# BrickPi_1_7_3.net
KiCad netlist of a schematic drawn in EAGLE
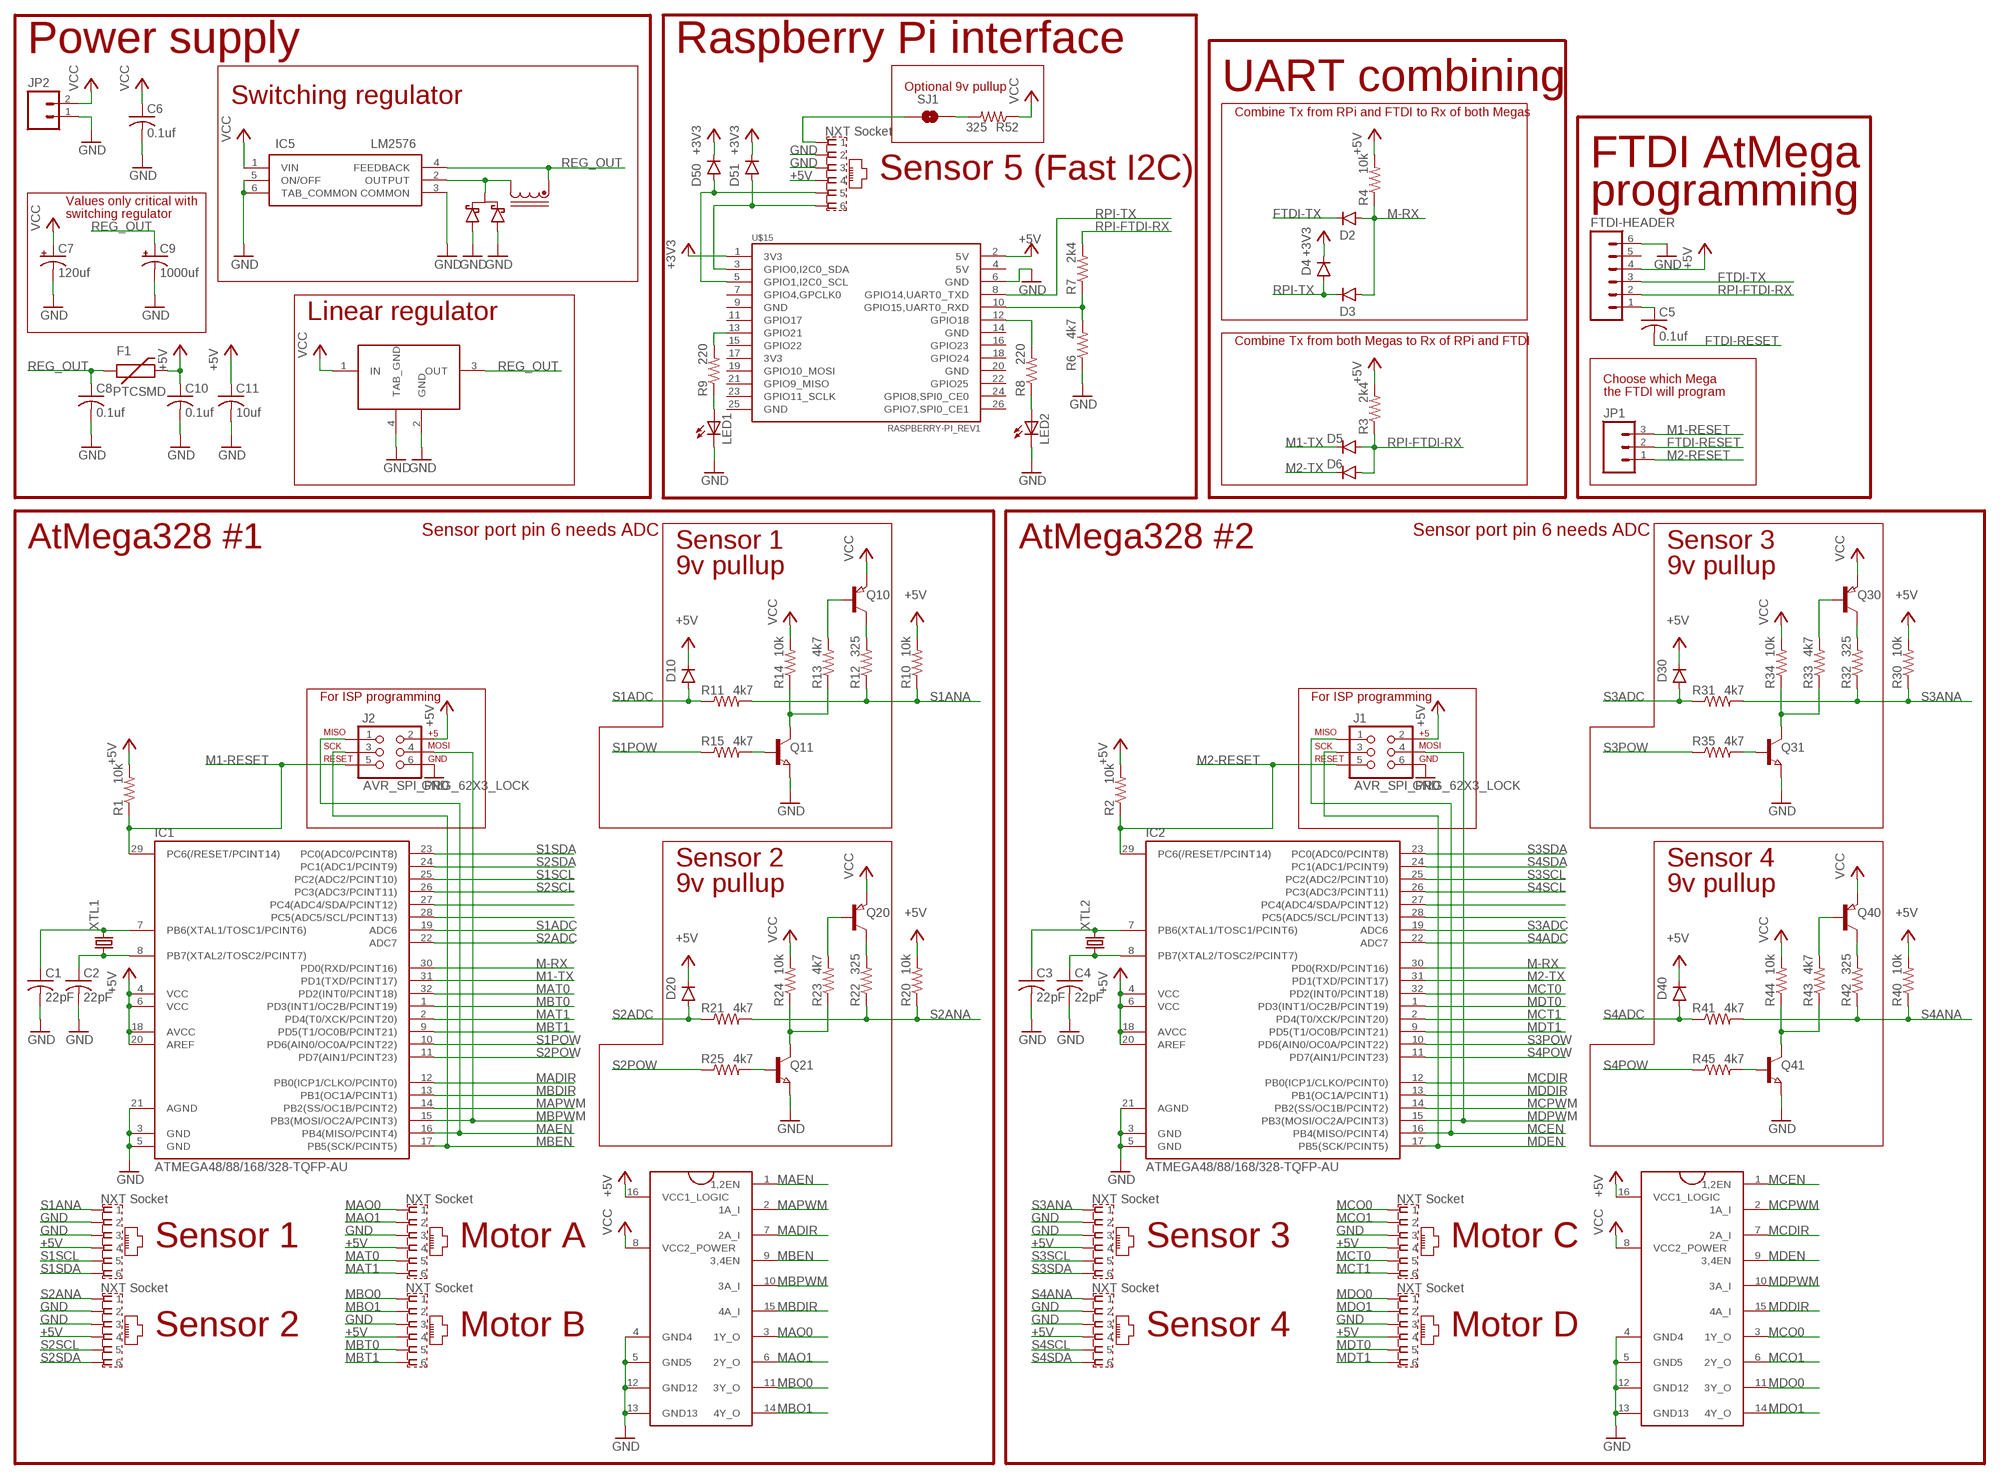
[diagram p0: schematic, sheet 1]

(export (version "E")
  (design (tool "Eeschema 10.0.6"))
  (components
    (comp (ref "C1")
      (value "22pF")
      (footprint "eagle-import:C0805")
      (libsource (lib "eagle-import") (part "C-USC0805"))
    )
    (comp (ref "C2")
      (value "22pF")
      (footprint "eagle-import:C0805")
      (libsource (lib "eagle-import") (part "C-USC0805"))
    )
    (comp (ref "C3")
      (value "22pF")
      (footprint "eagle-import:C0805")
      (libsource (lib "eagle-import") (part "C-USC0805"))
    )
    (comp (ref "C4")
      (value "22pF")
      (footprint "eagle-import:C0805")
      (libsource (lib "eagle-import") (part "C-USC0805"))
    )
    (comp (ref "C5")
      (value "0.1uf")
      (footprint "eagle-import:C0805")
      (libsource (lib "eagle-import") (part "C-USC0805"))
    )
    (comp (ref "C6")
      (value "0.1uf")
      (footprint "eagle-import:C0805")
      (libsource (lib "eagle-import") (part "C-USC0805"))
    )
    (comp (ref "C7")
      (value "120uf")
      (footprint "eagle-import:E2,5-6")
      (libsource (lib "eagle-import") (part "CPOL-USE2.5-6"))
    )
    (comp (ref "C8")
      (value "0.1uf")
      (footprint "eagle-import:C0805")
      (libsource (lib "eagle-import") (part "C-USC0805"))
    )
    (comp (ref "C9")
      (value "1000uf")
      (footprint "eagle-import:E3,5-10")
      (libsource (lib "eagle-import") (part "CPOL-USE3.5-10"))
    )
    (comp (ref "C10")
      (value "0.1uf")
      (footprint "eagle-import:C0805")
      (libsource (lib "eagle-import") (part "C-USC0805"))
    )
    (comp (ref "C11")
      (value "10uf")
      (footprint "eagle-import:C0805")
      (libsource (lib "eagle-import") (part "C-USC0805"))
    )
    (comp (ref "D1")
      (value "DIODE_SCHOTTKY_VS-6CWQ04FNTRPBF")
      (footprint "eagle-import:DPAK")
      (libsource (lib "eagle-import") (part "DIODE_SCHOTTKY_VS-6CWQ04FNTRPBF"))
    )
    (comp (ref "D2")
      (value "DIODESOD80")
      (footprint "eagle-import:SOD80")
      (libsource (lib "eagle-import") (part "DIODESOD80"))
    )
    (comp (ref "D3")
      (value "DIODESOD80")
      (footprint "eagle-import:SOD80")
      (libsource (lib "eagle-import") (part "DIODESOD80"))
    )
    (comp (ref "D4")
      (value "DIODESOD80")
      (footprint "eagle-import:SOD80")
      (libsource (lib "eagle-import") (part "DIODESOD80"))
    )
    (comp (ref "D5")
      (value "DIODESOD80")
      (footprint "eagle-import:SOD80")
      (libsource (lib "eagle-import") (part "DIODESOD80"))
    )
    (comp (ref "D6")
      (value "DIODESOD80")
      (footprint "eagle-import:SOD80")
      (libsource (lib "eagle-import") (part "DIODESOD80"))
    )
    (comp (ref "D10")
      (value "DIODESOD80")
      (footprint "eagle-import:SOD80")
      (libsource (lib "eagle-import") (part "DIODESOD80"))
    )
    (comp (ref "D20")
      (value "DIODESOD80")
      (footprint "eagle-import:SOD80")
      (libsource (lib "eagle-import") (part "DIODESOD80"))
    )
    (comp (ref "D30")
      (value "DIODESOD80")
      (footprint "eagle-import:SOD80")
      (libsource (lib "eagle-import") (part "DIODESOD80"))
    )
    (comp (ref "D40")
      (value "DIODESOD80")
      (footprint "eagle-import:SOD80")
      (libsource (lib "eagle-import") (part "DIODESOD80"))
    )
    (comp (ref "D50")
      (value "DIODESOD80")
      (footprint "eagle-import:SOD80")
      (libsource (lib "eagle-import") (part "DIODESOD80"))
    )
    (comp (ref "D51")
      (value "DIODESOD80")
      (footprint "eagle-import:SOD80")
      (libsource (lib "eagle-import") (part "DIODESOD80"))
    )
    (comp (ref "F1")
      (value "PTCSMD")
      (footprint "eagle-import:PTC-1206")
      (libsource (lib "eagle-import") (part "PTCSMD"))
    )
    (comp (ref "FTDI-HEADER")
      (value "M06LOCK")
      (footprint "eagle-import:1X06_LOCK")
      (libsource (lib "eagle-import") (part "M06LOCK"))
    )
    (comp (ref "IC1")
      (value "ATMEGA48/88/168/328-TQFP-AU")
      (footprint "eagle-import:TQFP32-08")
      (libsource (lib "eagle-import") (part "ATMEGA48/88/168/328-TQFP-AU"))
    )
    (comp (ref "IC2")
      (value "ATMEGA48/88/168/328-TQFP-AU")
      (footprint "eagle-import:TQFP32-08")
      (libsource (lib "eagle-import") (part "ATMEGA48/88/168/328-TQFP-AU"))
    )
    (comp (ref "IC3")
      (value "SN754410")
      (footprint "eagle-import:DIL16-ROUND-HEAT_DIS_SN754410")
      (libsource (lib "eagle-import") (part "SN754410"))
    )
    (comp (ref "IC4")
      (value "SN754410")
      (footprint "eagle-import:DIL16-ROUND-HEAT_DIS_SN754410")
      (libsource (lib "eagle-import") (part "SN754410"))
    )
    (comp (ref "IC5")
      (value "LM2576")
      (footprint "eagle-import:TO220-5-H")
      (libsource (lib "eagle-import") (part "REGULATOR_SWITCHING_LM2575_LM2576"))
    )
    (comp (ref "IC6")
      (value "REGULATOR_5V_TO220-H_7805")
      (footprint "eagle-import:TO220-H")
      (libsource (lib "eagle-import") (part "REGULATOR_5V_TO220-H_7805"))
    )
    (comp (ref "J1")
      (value "AVR_SPI_PRG_62X3_LOCK")
      (footprint "eagle-import:2X3_LOCK")
      (libsource (lib "eagle-import") (part "AVR_SPI_PRG_62X3_LOCK"))
    )
    (comp (ref "J2")
      (value "AVR_SPI_PRG_62X3_LOCK")
      (footprint "eagle-import:2X3_LOCK")
      (libsource (lib "eagle-import") (part "AVR_SPI_PRG_62X3_LOCK"))
    )
    (comp (ref "JP1")
      (value "M03LOCK")
      (footprint "eagle-import:1X03_LOCK")
      (libsource (lib "eagle-import") (part "M03LOCK"))
    )
    (comp (ref "JP2")
      (value "M02LOCK")
      (footprint "eagle-import:1X02_LOCK")
      (libsource (lib "eagle-import") (part "M02LOCK"))
    )
    (comp (ref "LED1")
      (value "LED0805")
      (footprint "eagle-import:0805-LED")
      (libsource (lib "eagle-import") (part "LED0805"))
    )
    (comp (ref "LED2")
      (value "LED0805")
      (footprint "eagle-import:0805-LED")
      (libsource (lib "eagle-import") (part "LED0805"))
    )
    (comp (ref "Q10")
      (value "PNP-TRANSISTOR_SOT23")
      (footprint "eagle-import:SOT23")
      (libsource (lib "eagle-import") (part "PNP-TRANSISTOR_SOT23"))
    )
    (comp (ref "Q11")
      (value "NPN-TRANSISTOR_SOT23")
      (footprint "eagle-import:SOT23")
      (libsource (lib "eagle-import") (part "NPN-TRANSISTOR_SOT23"))
    )
    (comp (ref "Q20")
      (value "PNP-TRANSISTOR_SOT23")
      (footprint "eagle-import:SOT23")
      (libsource (lib "eagle-import") (part "PNP-TRANSISTOR_SOT23"))
    )
    (comp (ref "Q21")
      (value "NPN-TRANSISTOR_SOT23")
      (footprint "eagle-import:SOT23")
      (libsource (lib "eagle-import") (part "NPN-TRANSISTOR_SOT23"))
    )
    (comp (ref "Q30")
      (value "PNP-TRANSISTOR_SOT23")
      (footprint "eagle-import:SOT23")
      (libsource (lib "eagle-import") (part "PNP-TRANSISTOR_SOT23"))
    )
    (comp (ref "Q31")
      (value "NPN-TRANSISTOR_SOT23")
      (footprint "eagle-import:SOT23")
      (libsource (lib "eagle-import") (part "NPN-TRANSISTOR_SOT23"))
    )
    (comp (ref "Q40")
      (value "PNP-TRANSISTOR_SOT23")
      (footprint "eagle-import:SOT23")
      (libsource (lib "eagle-import") (part "PNP-TRANSISTOR_SOT23"))
    )
    (comp (ref "Q41")
      (value "NPN-TRANSISTOR_SOT23")
      (footprint "eagle-import:SOT23")
      (libsource (lib "eagle-import") (part "NPN-TRANSISTOR_SOT23"))
    )
    (comp (ref "R1")
      (value "10k")
      (footprint "eagle-import:0603")
      (libsource (lib "eagle-import") (part "RESISTOR0603-RES"))
    )
    (comp (ref "R2")
      (value "10k")
      (footprint "eagle-import:0603")
      (libsource (lib "eagle-import") (part "RESISTOR0603-RES"))
    )
    (comp (ref "R3")
      (value "2k4")
      (footprint "eagle-import:0603")
      (libsource (lib "eagle-import") (part "RESISTOR0603-RES"))
    )
    (comp (ref "R4")
      (value "10k")
      (footprint "eagle-import:0603")
      (libsource (lib "eagle-import") (part "RESISTOR0603-RES"))
    )
    (comp (ref "R6")
      (value "4k7")
      (footprint "eagle-import:0603")
      (libsource (lib "eagle-import") (part "RESISTOR0603-RES"))
    )
    (comp (ref "R7")
      (value "2k4")
      (footprint "eagle-import:0603")
      (libsource (lib "eagle-import") (part "RESISTOR0603-RES"))
    )
    (comp (ref "R8")
      (value "220")
      (footprint "eagle-import:0603")
      (libsource (lib "eagle-import") (part "RESISTOR0603-RES"))
    )
    (comp (ref "R9")
      (value "220")
      (footprint "eagle-import:0603")
      (libsource (lib "eagle-import") (part "RESISTOR0603-RES"))
    )
    (comp (ref "R10")
      (value "10k")
      (footprint "eagle-import:0603")
      (libsource (lib "eagle-import") (part "RESISTOR0603-RES"))
    )
    (comp (ref "R11")
      (value "4k7")
      (footprint "eagle-import:0603")
      (libsource (lib "eagle-import") (part "RESISTOR0603-RES"))
    )
    (comp (ref "R12")
      (value "325")
      (footprint "eagle-import:1206")
      (libsource (lib "eagle-import") (part "RESISTOR1206"))
    )
    (comp (ref "R13")
      (value "4k7")
      (footprint "eagle-import:0603")
      (libsource (lib "eagle-import") (part "RESISTOR0603-RES"))
    )
    (comp (ref "R14")
      (value "10k")
      (footprint "eagle-import:0603")
      (libsource (lib "eagle-import") (part "RESISTOR0603-RES"))
    )
    (comp (ref "R15")
      (value "4k7")
      (footprint "eagle-import:0603")
      (libsource (lib "eagle-import") (part "RESISTOR0603-RES"))
    )
    (comp (ref "R20")
      (value "10k")
      (footprint "eagle-import:0603")
      (libsource (lib "eagle-import") (part "RESISTOR0603-RES"))
    )
    (comp (ref "R21")
      (value "4k7")
      (footprint "eagle-import:0603")
      (libsource (lib "eagle-import") (part "RESISTOR0603-RES"))
    )
    (comp (ref "R22")
      (value "325")
      (footprint "eagle-import:1206")
      (libsource (lib "eagle-import") (part "RESISTOR1206"))
    )
    (comp (ref "R23")
      (value "4k7")
      (footprint "eagle-import:0603")
      (libsource (lib "eagle-import") (part "RESISTOR0603-RES"))
    )
    (comp (ref "R24")
      (value "10k")
      (footprint "eagle-import:0603")
      (libsource (lib "eagle-import") (part "RESISTOR0603-RES"))
    )
    (comp (ref "R25")
      (value "4k7")
      (footprint "eagle-import:0603")
      (libsource (lib "eagle-import") (part "RESISTOR0603-RES"))
    )
    (comp (ref "R30")
      (value "10k")
      (footprint "eagle-import:0603")
      (libsource (lib "eagle-import") (part "RESISTOR0603-RES"))
    )
    (comp (ref "R31")
      (value "4k7")
      (footprint "eagle-import:0603")
      (libsource (lib "eagle-import") (part "RESISTOR0603-RES"))
    )
    (comp (ref "R32")
      (value "325")
      (footprint "eagle-import:1206")
      (libsource (lib "eagle-import") (part "RESISTOR1206"))
    )
    (comp (ref "R33")
      (value "4k7")
      (footprint "eagle-import:0603")
      (libsource (lib "eagle-import") (part "RESISTOR0603-RES"))
    )
    (comp (ref "R34")
      (value "10k")
      (footprint "eagle-import:0603")
      (libsource (lib "eagle-import") (part "RESISTOR0603-RES"))
    )
    (comp (ref "R35")
      (value "4k7")
      (footprint "eagle-import:0603")
      (libsource (lib "eagle-import") (part "RESISTOR0603-RES"))
    )
    (comp (ref "R40")
      (value "10k")
      (footprint "eagle-import:0603")
      (libsource (lib "eagle-import") (part "RESISTOR0603-RES"))
    )
    (comp (ref "R41")
      (value "4k7")
      (footprint "eagle-import:0603")
      (libsource (lib "eagle-import") (part "RESISTOR0603-RES"))
    )
    (comp (ref "R42")
      (value "325")
      (footprint "eagle-import:1206")
      (libsource (lib "eagle-import") (part "RESISTOR1206"))
    )
    (comp (ref "R43")
      (value "4k7")
      (footprint "eagle-import:0603")
      (libsource (lib "eagle-import") (part "RESISTOR0603-RES"))
    )
    (comp (ref "R44")
      (value "10k")
      (footprint "eagle-import:0603")
      (libsource (lib "eagle-import") (part "RESISTOR0603-RES"))
    )
    (comp (ref "R45")
      (value "4k7")
      (footprint "eagle-import:0603")
      (libsource (lib "eagle-import") (part "RESISTOR0603-RES"))
    )
    (comp (ref "R52")
      (value "325")
      (footprint "eagle-import:1206")
      (libsource (lib "eagle-import") (part "RESISTOR1206"))
    )
    (comp (ref "SJ1")
      (value "SOLDERJUMPERNO")
      (footprint "eagle-import:SJ_2")
      (libsource (lib "eagle-import") (part "SOLDERJUMPERNO"))
    )
    (comp (ref "U$3")
      (value "NXT-SOCKETREGULAR")
      (footprint "eagle-import:NXT-SOCKET")
      (libsource (lib "eagle-import") (part "NXT-SOCKETREGULAR"))
    )
    (comp (ref "U$4")
      (value "NXT-SOCKETREGULAR")
      (footprint "eagle-import:NXT-SOCKET")
      (libsource (lib "eagle-import") (part "NXT-SOCKETREGULAR"))
    )
    (comp (ref "U$5")
      (value "NXT-SOCKETREGULAR")
      (footprint "eagle-import:NXT-SOCKET")
      (libsource (lib "eagle-import") (part "NXT-SOCKETREGULAR"))
    )
    (comp (ref "U$7")
      (value "NXT-SOCKETREGULAR")
      (footprint "eagle-import:NXT-SOCKET")
      (libsource (lib "eagle-import") (part "NXT-SOCKETREGULAR"))
    )
    (comp (ref "U$8")
      (value "NXT-SOCKETREGULAR")
      (footprint "eagle-import:NXT-SOCKET")
      (libsource (lib "eagle-import") (part "NXT-SOCKETREGULAR"))
    )
    (comp (ref "U$9")
      (value "NXT-SOCKETREGULAR")
      (footprint "eagle-import:NXT-SOCKET")
      (libsource (lib "eagle-import") (part "NXT-SOCKETREGULAR"))
    )
    (comp (ref "U$10")
      (value "NXT-SOCKETREGULAR")
      (footprint "eagle-import:NXT-SOCKET")
      (libsource (lib "eagle-import") (part "NXT-SOCKETREGULAR"))
    )
    (comp (ref "U$11")
      (value "NXT-SOCKETREGULAR")
      (footprint "eagle-import:NXT-SOCKET")
      (libsource (lib "eagle-import") (part "NXT-SOCKETREGULAR"))
    )
    (comp (ref "U$12")
      (value "NXT-SOCKETREGULAR")
      (footprint "eagle-import:NXT-SOCKET")
      (libsource (lib "eagle-import") (part "NXT-SOCKETREGULAR"))
    )
    (comp (ref "U$14")
      (value "INDUCTOR_PULSE_P0250.XXXNL")
      (footprint "eagle-import:INDUCTOR_PULSE_P0250.XXXNL")
      (libsource (lib "eagle-import") (part "INDUCTOR_PULSE_P0250.XXXNL"))
    )
    (comp (ref "U$15")
      (value "RASPBERRY-PI_REV1")
      (footprint "eagle-import:RASPBERRY-PI_REV1")
      (libsource (lib "eagle-import") (part "RASPBERRY-PI_REV1"))
    )
    (comp (ref "XTL1")
      (value "CRYSTALHC49S")
      (footprint "eagle-import:HC49_S")
      (libsource (lib "eagle-import") (part "CRYSTALHC49S"))
    )
    (comp (ref "XTL2")
      (value "CRYSTALHC49S")
      (footprint "eagle-import:HC49_S")
      (libsource (lib "eagle-import") (part "CRYSTALHC49S"))
    )
  )
  (nets
    (net (code "1") (name "+3V3") (class "Default")
      (node (ref "D4") (pin "C") (pinfunction "C_C") (pintype "bidirectional"))
      (node (ref "D50") (pin "C") (pinfunction "C_C") (pintype "bidirectional"))
      (node (ref "D51") (pin "C") (pinfunction "C_C") (pintype "bidirectional"))
      (node (ref "U$15") (pin "1") (pinfunction "3V3_1") (pintype "bidirectional"))
    )
    (net (code "2") (name "+5V") (class "Default")
      (node (ref "C10") (pin "1") (pinfunction "1_1") (pintype "passive"))
      (node (ref "C11") (pin "1") (pinfunction "1_1") (pintype "passive"))
      (node (ref "D10") (pin "C") (pinfunction "C_C") (pintype "bidirectional"))
      (node (ref "D20") (pin "C") (pinfunction "C_C") (pintype "bidirectional"))
      (node (ref "D30") (pin "C") (pinfunction "C_C") (pintype "bidirectional"))
      (node (ref "D40") (pin "C") (pinfunction "C_C") (pintype "bidirectional"))
      (node (ref "F1") (pin "2") (pinfunction "2_2") (pintype "bidirectional"))
      (node (ref "FTDI-HEADER") (pin "4") (pinfunction "4_4") (pintype "passive"))
      (node (ref "IC1") (pin "18") (pinfunction "AVCC_18") (pintype "passive"))
      (node (ref "IC1") (pin "20") (pinfunction "AREF_20") (pintype "passive"))
      (node (ref "IC1") (pin "4") (pinfunction "VCC_4") (pintype "power_in"))
      (node (ref "IC1") (pin "6") (pinfunction "VCC_6") (pintype "power_in"))
      (node (ref "IC2") (pin "18") (pinfunction "AVCC_18") (pintype "passive"))
      (node (ref "IC2") (pin "20") (pinfunction "AREF_20") (pintype "passive"))
      (node (ref "IC2") (pin "4") (pinfunction "VCC_4") (pintype "power_in"))
      (node (ref "IC2") (pin "6") (pinfunction "VCC_6") (pintype "power_in"))
      (node (ref "IC3") (pin "16") (pinfunction "VCC1_LOGIC_16") (pintype "bidirectional"))
      (node (ref "IC4") (pin "16") (pinfunction "VCC1_LOGIC_16") (pintype "bidirectional"))
      (node (ref "J1") (pin "2") (pinfunction "2_2") (pintype "passive"))
      (node (ref "J2") (pin "2") (pinfunction "2_2") (pintype "passive"))
      (node (ref "R1") (pin "2") (pinfunction "2_2") (pintype "passive"))
      (node (ref "R10") (pin "2") (pinfunction "2_2") (pintype "passive"))
      (node (ref "R2") (pin "2") (pinfunction "2_2") (pintype "passive"))
      (node (ref "R20") (pin "2") (pinfunction "2_2") (pintype "passive"))
      (node (ref "R3") (pin "2") (pinfunction "2_2") (pintype "passive"))
      (node (ref "R30") (pin "2") (pinfunction "2_2") (pintype "passive"))
      (node (ref "R4") (pin "2") (pinfunction "2_2") (pintype "passive"))
      (node (ref "R40") (pin "2") (pinfunction "2_2") (pintype "passive"))
      (node (ref "U$10") (pin "4") (pinfunction "4_4") (pintype "passive"))
      (node (ref "U$11") (pin "4") (pinfunction "4_4") (pintype "passive"))
      (node (ref "U$12") (pin "4") (pinfunction "4_4") (pintype "passive"))
      (node (ref "U$15") (pin "2") (pinfunction "5V_2") (pintype "bidirectional"))
      (node (ref "U$3") (pin "4") (pinfunction "4_4") (pintype "passive"))
      (node (ref "U$4") (pin "4") (pinfunction "4_4") (pintype "passive"))
      (node (ref "U$5") (pin "4") (pinfunction "4_4") (pintype "passive"))
      (node (ref "U$7") (pin "4") (pinfunction "4_4") (pintype "passive"))
      (node (ref "U$8") (pin "4") (pinfunction "4_4") (pintype "passive"))
      (node (ref "U$9") (pin "4") (pinfunction "4_4") (pintype "passive"))
    )
    (net (code "3") (name "/FTDI-RESET") (class "Default")
      (node (ref "C5") (pin "2") (pinfunction "2_2") (pintype "passive"))
      (node (ref "JP1") (pin "2") (pinfunction "2_2") (pintype "passive"))
    )
    (net (code "4") (name "/FTDI-TX") (class "Default")
      (node (ref "D2") (pin "C") (pinfunction "C_C") (pintype "bidirectional"))
      (node (ref "FTDI-HEADER") (pin "3") (pinfunction "3_3") (pintype "passive"))
    )
    (net (code "5") (name "/M-RX") (class "Default")
      (node (ref "D2") (pin "A") (pinfunction "A_A") (pintype "bidirectional"))
      (node (ref "D3") (pin "A") (pinfunction "A_A") (pintype "bidirectional"))
      (node (ref "IC1") (pin "30") (pinfunction "PD0(RXD/PCINT16)_30") (pintype "bidirectional"))
      (node (ref "IC2") (pin "30") (pinfunction "PD0(RXD/PCINT16)_30") (pintype "bidirectional"))
      (node (ref "R4") (pin "1") (pinfunction "1_1") (pintype "passive"))
    )
    (net (code "6") (name "/M1-RESET") (class "Default")
      (node (ref "IC1") (pin "29") (pinfunction "PC6(/RESET/PCINT14)_29") (pintype "bidirectional"))
      (node (ref "J2") (pin "5") (pinfunction "5_5") (pintype "passive"))
      (node (ref "JP1") (pin "3") (pinfunction "3_3") (pintype "passive"))
      (node (ref "R1") (pin "1") (pinfunction "1_1") (pintype "passive"))
    )
    (net (code "7") (name "/M1-TX") (class "Default")
      (node (ref "D5") (pin "C") (pinfunction "C_C") (pintype "bidirectional"))
      (node (ref "IC1") (pin "31") (pinfunction "PD1(TXD/PCINT17)_31") (pintype "bidirectional"))
    )
    (net (code "8") (name "/M2-RESET") (class "Default")
      (node (ref "IC2") (pin "29") (pinfunction "PC6(/RESET/PCINT14)_29") (pintype "bidirectional"))
      (node (ref "J1") (pin "5") (pinfunction "5_5") (pintype "passive"))
      (node (ref "JP1") (pin "1") (pinfunction "1_1") (pintype "passive"))
      (node (ref "R2") (pin "1") (pinfunction "1_1") (pintype "passive"))
    )
    (net (code "9") (name "/M2-TX") (class "Default")
      (node (ref "D6") (pin "C") (pinfunction "C_C") (pintype "bidirectional"))
      (node (ref "IC2") (pin "31") (pinfunction "PD1(TXD/PCINT17)_31") (pintype "bidirectional"))
    )
    (net (code "10") (name "/MADIR") (class "Default")
      (node (ref "IC1") (pin "12") (pinfunction "PB0(ICP1/CLKO/PCINT0)_12") (pintype "bidirectional"))
      (node (ref "IC3") (pin "7") (pinfunction "2A_I_7") (pintype "bidirectional"))
    )
    (net (code "11") (name "/MAEN") (class "Default")
      (node (ref "IC1") (pin "16") (pinfunction "PB4(MISO/PCINT4)_16") (pintype "bidirectional"))
      (node (ref "IC3") (pin "1") (pinfunction "1,2EN_1") (pintype "bidirectional"))
      (node (ref "J2") (pin "1") (pinfunction "1_1") (pintype "passive"))
    )
    (net (code "12") (name "/MAO0") (class "Default")
      (node (ref "IC3") (pin "3") (pinfunction "1Y_O_3") (pintype "bidirectional"))
      (node (ref "U$3") (pin "1") (pinfunction "1_1") (pintype "passive"))
    )
    (net (code "13") (name "/MAO1") (class "Default")
      (node (ref "IC3") (pin "6") (pinfunction "2Y_O_6") (pintype "bidirectional"))
      (node (ref "U$3") (pin "2") (pinfunction "2_2") (pintype "passive"))
    )
    (net (code "14") (name "/MAPWM") (class "Default")
      (node (ref "IC1") (pin "14") (pinfunction "PB2(SS/OC1B/PCINT2)_14") (pintype "bidirectional"))
      (node (ref "IC3") (pin "2") (pinfunction "1A_I_2") (pintype "bidirectional"))
    )
    (net (code "15") (name "/MAT0") (class "Default")
      (node (ref "IC1") (pin "32") (pinfunction "PD2(INT0/PCINT18)_32") (pintype "bidirectional"))
      (node (ref "U$3") (pin "5") (pinfunction "5_5") (pintype "passive"))
    )
    (net (code "16") (name "/MAT1") (class "Default")
      (node (ref "IC1") (pin "2") (pinfunction "PD4(T0/XCK/PCINT20)_2") (pintype "bidirectional"))
      (node (ref "U$3") (pin "6") (pinfunction "6_6") (pintype "passive"))
    )
    (net (code "17") (name "/MBDIR") (class "Default")
      (node (ref "IC1") (pin "13") (pinfunction "PB1(OC1A/PCINT1)_13") (pintype "bidirectional"))
      (node (ref "IC3") (pin "15") (pinfunction "4A_I_15") (pintype "bidirectional"))
    )
    (net (code "18") (name "/MBEN") (class "Default")
      (node (ref "IC1") (pin "17") (pinfunction "PB5(SCK/PCINT5)_17") (pintype "bidirectional"))
      (node (ref "IC3") (pin "9") (pinfunction "3,4EN_9") (pintype "bidirectional"))
      (node (ref "J2") (pin "3") (pinfunction "3_3") (pintype "passive"))
    )
    (net (code "19") (name "/MBO0") (class "Default")
      (node (ref "IC3") (pin "11") (pinfunction "3Y_O_11") (pintype "bidirectional"))
      (node (ref "U$4") (pin "1") (pinfunction "1_1") (pintype "passive"))
    )
    (net (code "20") (name "/MBO1") (class "Default")
      (node (ref "IC3") (pin "14") (pinfunction "4Y_O_14") (pintype "bidirectional"))
      (node (ref "U$4") (pin "2") (pinfunction "2_2") (pintype "passive"))
    )
    (net (code "21") (name "/MBPWM") (class "Default")
      (node (ref "IC1") (pin "15") (pinfunction "PB3(MOSI/OC2A/PCINT3)_15") (pintype "bidirectional"))
      (node (ref "IC3") (pin "10") (pinfunction "3A_I_10") (pintype "bidirectional"))
      (node (ref "J2") (pin "4") (pinfunction "4_4") (pintype "passive"))
    )
    (net (code "22") (name "/MBT0") (class "Default")
      (node (ref "IC1") (pin "1") (pinfunction "PD3(INT1/OC2B/PCINT19)_1") (pintype "bidirectional"))
      (node (ref "U$4") (pin "5") (pinfunction "5_5") (pintype "passive"))
    )
    (net (code "23") (name "/MBT1") (class "Default")
      (node (ref "IC1") (pin "9") (pinfunction "PD5(T1/OC0B/PCINT21)_9") (pintype "bidirectional"))
      (node (ref "U$4") (pin "6") (pinfunction "6_6") (pintype "passive"))
    )
    (net (code "24") (name "/MCDIR") (class "Default")
      (node (ref "IC2") (pin "12") (pinfunction "PB0(ICP1/CLKO/PCINT0)_12") (pintype "bidirectional"))
      (node (ref "IC4") (pin "7") (pinfunction "2A_I_7") (pintype "bidirectional"))
    )
    (net (code "25") (name "/MCEN") (class "Default")
      (node (ref "IC2") (pin "16") (pinfunction "PB4(MISO/PCINT4)_16") (pintype "bidirectional"))
      (node (ref "IC4") (pin "1") (pinfunction "1,2EN_1") (pintype "bidirectional"))
      (node (ref "J1") (pin "1") (pinfunction "1_1") (pintype "passive"))
    )
    (net (code "26") (name "/MCO0") (class "Default")
      (node (ref "IC4") (pin "3") (pinfunction "1Y_O_3") (pintype "bidirectional"))
      (node (ref "U$5") (pin "1") (pinfunction "1_1") (pintype "passive"))
    )
    (net (code "27") (name "/MCO1") (class "Default")
      (node (ref "IC4") (pin "6") (pinfunction "2Y_O_6") (pintype "bidirectional"))
      (node (ref "U$5") (pin "2") (pinfunction "2_2") (pintype "passive"))
    )
    (net (code "28") (name "/MCPWM") (class "Default")
      (node (ref "IC2") (pin "14") (pinfunction "PB2(SS/OC1B/PCINT2)_14") (pintype "bidirectional"))
      (node (ref "IC4") (pin "2") (pinfunction "1A_I_2") (pintype "bidirectional"))
    )
    (net (code "29") (name "/MCT0") (class "Default")
      (node (ref "IC2") (pin "32") (pinfunction "PD2(INT0/PCINT18)_32") (pintype "bidirectional"))
      (node (ref "U$5") (pin "5") (pinfunction "5_5") (pintype "passive"))
    )
    (net (code "30") (name "/MCT1") (class "Default")
      (node (ref "IC2") (pin "2") (pinfunction "PD4(T0/XCK/PCINT20)_2") (pintype "bidirectional"))
      (node (ref "U$5") (pin "6") (pinfunction "6_6") (pintype "passive"))
    )
    (net (code "31") (name "/MDDIR") (class "Default")
      (node (ref "IC2") (pin "13") (pinfunction "PB1(OC1A/PCINT1)_13") (pintype "bidirectional"))
      (node (ref "IC4") (pin "15") (pinfunction "4A_I_15") (pintype "bidirectional"))
    )
    (net (code "32") (name "/MDEN") (class "Default")
      (node (ref "IC2") (pin "17") (pinfunction "PB5(SCK/PCINT5)_17") (pintype "bidirectional"))
      (node (ref "IC4") (pin "9") (pinfunction "3,4EN_9") (pintype "bidirectional"))
      (node (ref "J1") (pin "3") (pinfunction "3_3") (pintype "passive"))
    )
    (net (code "33") (name "/MDO0") (class "Default")
      (node (ref "IC4") (pin "11") (pinfunction "3Y_O_11") (pintype "bidirectional"))
      (node (ref "U$7") (pin "1") (pinfunction "1_1") (pintype "passive"))
    )
    (net (code "34") (name "/MDO1") (class "Default")
      (node (ref "IC4") (pin "14") (pinfunction "4Y_O_14") (pintype "bidirectional"))
      (node (ref "U$7") (pin "2") (pinfunction "2_2") (pintype "passive"))
    )
    (net (code "35") (name "/MDPWM") (class "Default")
      (node (ref "IC2") (pin "15") (pinfunction "PB3(MOSI/OC2A/PCINT3)_15") (pintype "bidirectional"))
      (node (ref "IC4") (pin "10") (pinfunction "3A_I_10") (pintype "bidirectional"))
      (node (ref "J1") (pin "4") (pinfunction "4_4") (pintype "passive"))
    )
    (net (code "36") (name "/MDT0") (class "Default")
      (node (ref "IC2") (pin "1") (pinfunction "PD3(INT1/OC2B/PCINT19)_1") (pintype "bidirectional"))
      (node (ref "U$7") (pin "5") (pinfunction "5_5") (pintype "passive"))
    )
    (net (code "37") (name "/MDT1") (class "Default")
      (node (ref "IC2") (pin "9") (pinfunction "PD5(T1/OC0B/PCINT21)_9") (pintype "bidirectional"))
      (node (ref "U$7") (pin "6") (pinfunction "6_6") (pintype "passive"))
    )
    (net (code "38") (name "/REG_OUT") (class "Default")
      (node (ref "C8") (pin "1") (pinfunction "1_1") (pintype "passive"))
      (node (ref "C9") (pin "+") (pinfunction "+_+") (pintype "passive"))
      (node (ref "F1") (pin "1") (pinfunction "1_1") (pintype "bidirectional"))
      (node (ref "IC5") (pin "4") (pinfunction "FEEDBACK_4") (pintype "bidirectional"))
      (node (ref "IC6") (pin "3") (pinfunction "OUT_3") (pintype "bidirectional"))
      (node (ref "U$14") (pin "P$1") (pinfunction "P$1_P$1") (pintype "bidirectional"))
    )
    (net (code "39") (name "/RPI-FTDI-RX") (class "Default")
      (node (ref "D5") (pin "A") (pinfunction "A_A") (pintype "bidirectional"))
      (node (ref "D6") (pin "A") (pinfunction "A_A") (pintype "bidirectional"))
      (node (ref "FTDI-HEADER") (pin "2") (pinfunction "2_2") (pintype "passive"))
      (node (ref "R3") (pin "1") (pinfunction "1_1") (pintype "passive"))
      (node (ref "R7") (pin "2") (pinfunction "2_2") (pintype "passive"))
    )
    (net (code "40") (name "/RPI-TX") (class "Default")
      (node (ref "D3") (pin "C") (pinfunction "C_C") (pintype "bidirectional"))
      (node (ref "D4") (pin "A") (pinfunction "A_A") (pintype "bidirectional"))
      (node (ref "U$15") (pin "8") (pinfunction "GPIO14,UART0_TXD_8") (pintype "bidirectional"))
    )
    (net (code "41") (name "/S1ADC") (class "Default")
      (node (ref "D10") (pin "A") (pinfunction "A_A") (pintype "bidirectional"))
      (node (ref "IC1") (pin "19") (pinfunction "ADC6_19") (pintype "passive"))
      (node (ref "R11") (pin "1") (pinfunction "1_1") (pintype "passive"))
    )
    (net (code "42") (name "/S1ANA") (class "Default")
      (node (ref "R10") (pin "1") (pinfunction "1_1") (pintype "passive"))
      (node (ref "R11") (pin "2") (pinfunction "2_2") (pintype "passive"))
      (node (ref "R12") (pin "1") (pinfunction "1_1") (pintype "passive"))
      (node (ref "U$8") (pin "1") (pinfunction "1_1") (pintype "passive"))
    )
    (net (code "43") (name "/S1POW") (class "Default")
      (node (ref "IC1") (pin "10") (pinfunction "PD6(AIN0/OC0A/PCINT22)_10") (pintype "bidirectional"))
      (node (ref "R15") (pin "1") (pinfunction "1_1") (pintype "passive"))
    )
    (net (code "44") (name "/S1SCL") (class "Default")
      (node (ref "IC1") (pin "25") (pinfunction "PC2(ADC2/PCINT10)_25") (pintype "bidirectional"))
      (node (ref "U$8") (pin "5") (pinfunction "5_5") (pintype "passive"))
    )
    (net (code "45") (name "/S1SDA") (class "Default")
      (node (ref "IC1") (pin "23") (pinfunction "PC0(ADC0/PCINT8)_23") (pintype "bidirectional"))
      (node (ref "U$8") (pin "6") (pinfunction "6_6") (pintype "passive"))
    )
    (net (code "46") (name "/S2ADC") (class "Default")
      (node (ref "D20") (pin "A") (pinfunction "A_A") (pintype "bidirectional"))
      (node (ref "IC1") (pin "22") (pinfunction "ADC7_22") (pintype "passive"))
      (node (ref "R21") (pin "1") (pinfunction "1_1") (pintype "passive"))
    )
    (net (code "47") (name "/S2ANA") (class "Default")
      (node (ref "R20") (pin "1") (pinfunction "1_1") (pintype "passive"))
      (node (ref "R21") (pin "2") (pinfunction "2_2") (pintype "passive"))
      (node (ref "R22") (pin "1") (pinfunction "1_1") (pintype "passive"))
      (node (ref "U$9") (pin "1") (pinfunction "1_1") (pintype "passive"))
    )
    (net (code "48") (name "/S2POW") (class "Default")
      (node (ref "IC1") (pin "11") (pinfunction "PD7(AIN1/PCINT23)_11") (pintype "bidirectional"))
      (node (ref "R25") (pin "1") (pinfunction "1_1") (pintype "passive"))
    )
    (net (code "49") (name "/S2SCL") (class "Default")
      (node (ref "IC1") (pin "26") (pinfunction "PC3(ADC3/PCINT11)_26") (pintype "bidirectional"))
      (node (ref "U$9") (pin "5") (pinfunction "5_5") (pintype "passive"))
    )
    (net (code "50") (name "/S2SDA") (class "Default")
      (node (ref "IC1") (pin "24") (pinfunction "PC1(ADC1/PCINT9)_24") (pintype "bidirectional"))
      (node (ref "U$9") (pin "6") (pinfunction "6_6") (pintype "passive"))
    )
    (net (code "51") (name "/S3ADC") (class "Default")
      (node (ref "D30") (pin "A") (pinfunction "A_A") (pintype "bidirectional"))
      (node (ref "IC2") (pin "19") (pinfunction "ADC6_19") (pintype "passive"))
      (node (ref "R31") (pin "1") (pinfunction "1_1") (pintype "passive"))
    )
    (net (code "52") (name "/S3ANA") (class "Default")
      (node (ref "R30") (pin "1") (pinfunction "1_1") (pintype "passive"))
      (node (ref "R31") (pin "2") (pinfunction "2_2") (pintype "passive"))
      (node (ref "R32") (pin "1") (pinfunction "1_1") (pintype "passive"))
      (node (ref "U$10") (pin "1") (pinfunction "1_1") (pintype "passive"))
    )
    (net (code "53") (name "/S3POW") (class "Default")
      (node (ref "IC2") (pin "10") (pinfunction "PD6(AIN0/OC0A/PCINT22)_10") (pintype "bidirectional"))
      (node (ref "R35") (pin "1") (pinfunction "1_1") (pintype "passive"))
    )
    (net (code "54") (name "/S3SCL") (class "Default")
      (node (ref "IC2") (pin "25") (pinfunction "PC2(ADC2/PCINT10)_25") (pintype "bidirectional"))
      (node (ref "U$10") (pin "5") (pinfunction "5_5") (pintype "passive"))
    )
    (net (code "55") (name "/S3SDA") (class "Default")
      (node (ref "IC2") (pin "23") (pinfunction "PC0(ADC0/PCINT8)_23") (pintype "bidirectional"))
      (node (ref "U$10") (pin "6") (pinfunction "6_6") (pintype "passive"))
    )
    (net (code "56") (name "/S4ADC") (class "Default")
      (node (ref "D40") (pin "A") (pinfunction "A_A") (pintype "bidirectional"))
      (node (ref "IC2") (pin "22") (pinfunction "ADC7_22") (pintype "passive"))
      (node (ref "R41") (pin "1") (pinfunction "1_1") (pintype "passive"))
    )
    (net (code "57") (name "/S4ANA") (class "Default")
      (node (ref "R40") (pin "1") (pinfunction "1_1") (pintype "passive"))
      (node (ref "R41") (pin "2") (pinfunction "2_2") (pintype "passive"))
      (node (ref "R42") (pin "1") (pinfunction "1_1") (pintype "passive"))
      (node (ref "U$11") (pin "1") (pinfunction "1_1") (pintype "passive"))
    )
    (net (code "58") (name "/S4POW") (class "Default")
      (node (ref "IC2") (pin "11") (pinfunction "PD7(AIN1/PCINT23)_11") (pintype "bidirectional"))
      (node (ref "R45") (pin "1") (pinfunction "1_1") (pintype "passive"))
    )
    (net (code "59") (name "/S4SCL") (class "Default")
      (node (ref "IC2") (pin "26") (pinfunction "PC3(ADC3/PCINT11)_26") (pintype "bidirectional"))
      (node (ref "U$11") (pin "5") (pinfunction "5_5") (pintype "passive"))
    )
    (net (code "60") (name "/S4SDA") (class "Default")
      (node (ref "IC2") (pin "24") (pinfunction "PC1(ADC1/PCINT9)_24") (pintype "bidirectional"))
      (node (ref "U$11") (pin "6") (pinfunction "6_6") (pintype "passive"))
    )
    (net (code "61") (name "GND") (class "Default")
      (node (ref "C1") (pin "2") (pinfunction "2_2") (pintype "passive"))
      (node (ref "C10") (pin "2") (pinfunction "2_2") (pintype "passive"))
      (node (ref "C11") (pin "2") (pinfunction "2_2") (pintype "passive"))
      (node (ref "C2") (pin "2") (pinfunction "2_2") (pintype "passive"))
      (node (ref "C3") (pin "2") (pinfunction "2_2") (pintype "passive"))
      (node (ref "C4") (pin "2") (pinfunction "2_2") (pintype "passive"))
      (node (ref "C6") (pin "2") (pinfunction "2_2") (pintype "passive"))
      (node (ref "C7") (pin "-") (pinfunction "-_-") (pintype "passive"))
      (node (ref "C8") (pin "2") (pinfunction "2_2") (pintype "passive"))
      (node (ref "C9") (pin "-") (pinfunction "-_-") (pintype "passive"))
      (node (ref "D1") (pin "1") (pinfunction "P$1_1") (pintype "bidirectional"))
      (node (ref "D1") (pin "3") (pinfunction "P$3_3") (pintype "bidirectional"))
      (node (ref "FTDI-HEADER") (pin "6") (pinfunction "6_6") (pintype "passive"))
      (node (ref "IC1") (pin "21") (pinfunction "AGND_21") (pintype "power_in"))
      (node (ref "IC1") (pin "3") (pinfunction "GND_3") (pintype "power_in"))
      (node (ref "IC1") (pin "5") (pinfunction "GND_5") (pintype "power_in"))
      (node (ref "IC2") (pin "21") (pinfunction "AGND_21") (pintype "power_in"))
      (node (ref "IC2") (pin "3") (pinfunction "GND_3") (pintype "power_in"))
      (node (ref "IC2") (pin "5") (pinfunction "GND_5") (pintype "power_in"))
      (node (ref "IC3") (pin "12") (pinfunction "GND12_12") (pintype "bidirectional"))
      (node (ref "IC3") (pin "13") (pinfunction "GND13_13") (pintype "bidirectional"))
      (node (ref "IC3") (pin "4") (pinfunction "GND4_4") (pintype "bidirectional"))
      (node (ref "IC3") (pin "5") (pinfunction "GND5_5") (pintype "bidirectional"))
      (node (ref "IC4") (pin "12") (pinfunction "GND12_12") (pintype "bidirectional"))
      (node (ref "IC4") (pin "13") (pinfunction "GND13_13") (pintype "bidirectional"))
      (node (ref "IC4") (pin "4") (pinfunction "GND4_4") (pintype "bidirectional"))
      (node (ref "IC4") (pin "5") (pinfunction "GND5_5") (pintype "bidirectional"))
      (node (ref "IC5") (pin "3") (pinfunction "COMMON_3") (pintype "bidirectional"))
      (node (ref "IC5") (pin "5") (pinfunction "ON/OFF_5") (pintype "bidirectional"))
      (node (ref "IC5") (pin "6") (pinfunction "TAB_COMMON_6") (pintype "bidirectional"))
      (node (ref "IC6") (pin "2") (pinfunction "GND_2") (pintype "bidirectional"))
      (node (ref "IC6") (pin "4") (pinfunction "TAB_GND_4") (pintype "bidirectional"))
      (node (ref "J1") (pin "6") (pinfunction "6_6") (pintype "passive"))
      (node (ref "J2") (pin "6") (pinfunction "6_6") (pintype "passive"))
      (node (ref "JP2") (pin "1") (pinfunction "1_1") (pintype "passive"))
      (node (ref "LED1") (pin "2") (pinfunction "C_2") (pintype "passive"))
      (node (ref "LED2") (pin "2") (pinfunction "C_2") (pintype "passive"))
      (node (ref "Q11") (pin "2") (pinfunction "E_2") (pintype "passive"))
      (node (ref "Q21") (pin "2") (pinfunction "E_2") (pintype "passive"))
      (node (ref "Q31") (pin "2") (pinfunction "E_2") (pintype "passive"))
      (node (ref "Q41") (pin "2") (pinfunction "E_2") (pintype "passive"))
      (node (ref "R6") (pin "1") (pinfunction "1_1") (pintype "passive"))
      (node (ref "U$10") (pin "2") (pinfunction "2_2") (pintype "passive"))
      (node (ref "U$10") (pin "3") (pinfunction "3_3") (pintype "passive"))
      (node (ref "U$11") (pin "2") (pinfunction "2_2") (pintype "passive"))
      (node (ref "U$11") (pin "3") (pinfunction "3_3") (pintype "passive"))
      (node (ref "U$12") (pin "2") (pinfunction "2_2") (pintype "passive"))
      (node (ref "U$12") (pin "3") (pinfunction "3_3") (pintype "passive"))
      (node (ref "U$15") (pin "6") (pinfunction "GND_6") (pintype "bidirectional"))
      (node (ref "U$3") (pin "3") (pinfunction "3_3") (pintype "passive"))
      (node (ref "U$4") (pin "3") (pinfunction "3_3") (pintype "passive"))
      (node (ref "U$5") (pin "3") (pinfunction "3_3") (pintype "passive"))
      (node (ref "U$7") (pin "3") (pinfunction "3_3") (pintype "passive"))
      (node (ref "U$8") (pin "2") (pinfunction "2_2") (pintype "passive"))
      (node (ref "U$8") (pin "3") (pinfunction "3_3") (pintype "passive"))
      (node (ref "U$9") (pin "2") (pinfunction "2_2") (pintype "passive"))
      (node (ref "U$9") (pin "3") (pinfunction "3_3") (pintype "passive"))
    )
    (net (code "62") (name "Net-(C5-Pad1)") (class "Default")
      (node (ref "C5") (pin "1") (pinfunction "1_1") (pintype "passive"))
      (node (ref "FTDI-HEADER") (pin "1") (pinfunction "1_1") (pintype "passive"))
    )
    (net (code "63") (name "Net-(D1-P$2)") (class "Default")
      (node (ref "D1") (pin "4") (pinfunction "P$2_4") (pintype "bidirectional"))
      (node (ref "IC5") (pin "2") (pinfunction "OUTPUT_2") (pintype "bidirectional"))
      (node (ref "U$14") (pin "P$2") (pinfunction "P$2_P$2") (pintype "bidirectional"))
    )
    (net (code "64") (name "Net-(IC1-PB6(XTAL1{slash}TOSC1{slash}PCINT6))") (class "Default")
      (node (ref "C1") (pin "1") (pinfunction "1_1") (pintype "passive"))
      (node (ref "IC1") (pin "7") (pinfunction "PB6(XTAL1/TOSC1/PCINT6)_7") (pintype "bidirectional"))
      (node (ref "XTL1") (pin "2") (pinfunction "2_2") (pintype "passive"))
    )
    (net (code "65") (name "Net-(IC1-PB7(XTAL2{slash}TOSC2{slash}PCINT7))") (class "Default")
      (node (ref "C2") (pin "1") (pinfunction "1_1") (pintype "passive"))
      (node (ref "IC1") (pin "8") (pinfunction "PB7(XTAL2/TOSC2/PCINT7)_8") (pintype "bidirectional"))
      (node (ref "XTL1") (pin "1") (pinfunction "1_1") (pintype "passive"))
    )
    (net (code "66") (name "Net-(IC2-PB6(XTAL1{slash}TOSC1{slash}PCINT6))") (class "Default")
      (node (ref "C3") (pin "1") (pinfunction "1_1") (pintype "passive"))
      (node (ref "IC2") (pin "7") (pinfunction "PB6(XTAL1/TOSC1/PCINT6)_7") (pintype "bidirectional"))
      (node (ref "XTL2") (pin "2") (pinfunction "2_2") (pintype "passive"))
    )
    (net (code "67") (name "Net-(IC2-PB7(XTAL2{slash}TOSC2{slash}PCINT7))") (class "Default")
      (node (ref "C4") (pin "1") (pinfunction "1_1") (pintype "passive"))
      (node (ref "IC2") (pin "8") (pinfunction "PB7(XTAL2/TOSC2/PCINT7)_8") (pintype "bidirectional"))
      (node (ref "XTL2") (pin "1") (pinfunction "1_1") (pintype "passive"))
    )
    (net (code "68") (name "Net-(LED1-A)") (class "Default")
      (node (ref "LED1") (pin "1") (pinfunction "A_1") (pintype "passive"))
      (node (ref "R9") (pin "1") (pinfunction "1_1") (pintype "passive"))
    )
    (net (code "69") (name "Net-(LED2-A)") (class "Default")
      (node (ref "LED2") (pin "1") (pinfunction "A_1") (pintype "passive"))
      (node (ref "R8") (pin "1") (pinfunction "1_1") (pintype "passive"))
    )
    (net (code "70") (name "Net-(Q10-B)") (class "Default")
      (node (ref "Q10") (pin "1") (pinfunction "B_1") (pintype "passive"))
      (node (ref "R13") (pin "2") (pinfunction "2_2") (pintype "passive"))
    )
    (net (code "71") (name "Net-(Q10-C)") (class "Default")
      (node (ref "Q10") (pin "3") (pinfunction "C_3") (pintype "passive"))
      (node (ref "R12") (pin "2") (pinfunction "2_2") (pintype "passive"))
    )
    (net (code "72") (name "Net-(Q11-B)") (class "Default")
      (node (ref "Q11") (pin "1") (pinfunction "B_1") (pintype "passive"))
      (node (ref "R15") (pin "2") (pinfunction "2_2") (pintype "passive"))
    )
    (net (code "73") (name "Net-(Q11-C)") (class "Default")
      (node (ref "Q11") (pin "3") (pinfunction "C_3") (pintype "passive"))
      (node (ref "R13") (pin "1") (pinfunction "1_1") (pintype "passive"))
      (node (ref "R14") (pin "1") (pinfunction "1_1") (pintype "passive"))
    )
    (net (code "74") (name "Net-(Q20-B)") (class "Default")
      (node (ref "Q20") (pin "1") (pinfunction "B_1") (pintype "passive"))
      (node (ref "R23") (pin "2") (pinfunction "2_2") (pintype "passive"))
    )
    (net (code "75") (name "Net-(Q20-C)") (class "Default")
      (node (ref "Q20") (pin "3") (pinfunction "C_3") (pintype "passive"))
      (node (ref "R22") (pin "2") (pinfunction "2_2") (pintype "passive"))
    )
    (net (code "76") (name "Net-(Q21-B)") (class "Default")
      (node (ref "Q21") (pin "1") (pinfunction "B_1") (pintype "passive"))
      (node (ref "R25") (pin "2") (pinfunction "2_2") (pintype "passive"))
    )
    (net (code "77") (name "Net-(Q21-C)") (class "Default")
      (node (ref "Q21") (pin "3") (pinfunction "C_3") (pintype "passive"))
      (node (ref "R23") (pin "1") (pinfunction "1_1") (pintype "passive"))
      (node (ref "R24") (pin "1") (pinfunction "1_1") (pintype "passive"))
    )
    (net (code "78") (name "Net-(Q30-B)") (class "Default")
      (node (ref "Q30") (pin "1") (pinfunction "B_1") (pintype "passive"))
      (node (ref "R33") (pin "2") (pinfunction "2_2") (pintype "passive"))
    )
    (net (code "79") (name "Net-(Q30-C)") (class "Default")
      (node (ref "Q30") (pin "3") (pinfunction "C_3") (pintype "passive"))
      (node (ref "R32") (pin "2") (pinfunction "2_2") (pintype "passive"))
    )
    (net (code "80") (name "Net-(Q31-B)") (class "Default")
      (node (ref "Q31") (pin "1") (pinfunction "B_1") (pintype "passive"))
      (node (ref "R35") (pin "2") (pinfunction "2_2") (pintype "passive"))
    )
    (net (code "81") (name "Net-(Q31-C)") (class "Default")
      (node (ref "Q31") (pin "3") (pinfunction "C_3") (pintype "passive"))
      (node (ref "R33") (pin "1") (pinfunction "1_1") (pintype "passive"))
      (node (ref "R34") (pin "1") (pinfunction "1_1") (pintype "passive"))
    )
    (net (code "82") (name "Net-(Q40-B)") (class "Default")
      (node (ref "Q40") (pin "1") (pinfunction "B_1") (pintype "passive"))
      (node (ref "R43") (pin "2") (pinfunction "2_2") (pintype "passive"))
    )
    (net (code "83") (name "Net-(Q40-C)") (class "Default")
      (node (ref "Q40") (pin "3") (pinfunction "C_3") (pintype "passive"))
      (node (ref "R42") (pin "2") (pinfunction "2_2") (pintype "passive"))
    )
    (net (code "84") (name "Net-(Q41-B)") (class "Default")
      (node (ref "Q41") (pin "1") (pinfunction "B_1") (pintype "passive"))
      (node (ref "R45") (pin "2") (pinfunction "2_2") (pintype "passive"))
    )
    (net (code "85") (name "Net-(Q41-C)") (class "Default")
      (node (ref "Q41") (pin "3") (pinfunction "C_3") (pintype "passive"))
      (node (ref "R43") (pin "1") (pinfunction "1_1") (pintype "passive"))
      (node (ref "R44") (pin "1") (pinfunction "1_1") (pintype "passive"))
    )
    (net (code "86") (name "Net-(R52-Pad2)") (class "Default")
      (node (ref "R52") (pin "2") (pinfunction "2_2") (pintype "passive"))
      (node (ref "SJ1") (pin "2") (pinfunction "2_2") (pintype "passive"))
    )
    (net (code "87") (name "Net-(SJ1-Pad1)") (class "Default")
      (node (ref "SJ1") (pin "1") (pinfunction "1_1") (pintype "passive"))
      (node (ref "U$12") (pin "1") (pinfunction "1_1") (pintype "passive"))
    )
    (net (code "88") (name "Net-(U$15-GPIO0,I2C0_SDA)") (class "Default")
      (node (ref "D51") (pin "A") (pinfunction "A_A") (pintype "bidirectional"))
      (node (ref "U$12") (pin "6") (pinfunction "6_6") (pintype "passive"))
      (node (ref "U$15") (pin "3") (pinfunction "GPIO0,I2C0_SDA_3") (pintype "bidirectional"))
    )
    (net (code "89") (name "Net-(U$15-GPIO1,I2C0_SCL)") (class "Default")
      (node (ref "D50") (pin "A") (pinfunction "A_A") (pintype "bidirectional"))
      (node (ref "U$12") (pin "5") (pinfunction "5_5") (pintype "passive"))
      (node (ref "U$15") (pin "5") (pinfunction "GPIO1,I2C0_SCL_5") (pintype "bidirectional"))
    )
    (net (code "90") (name "Net-(U$15-GPIO15,UART0_RXD)") (class "Default")
      (node (ref "R6") (pin "2") (pinfunction "2_2") (pintype "passive"))
      (node (ref "R7") (pin "1") (pinfunction "1_1") (pintype "passive"))
      (node (ref "U$15") (pin "10") (pinfunction "GPIO15,UART0_RXD_10") (pintype "bidirectional"))
    )
    (net (code "91") (name "Net-(U$15-GPIO18)") (class "Default")
      (node (ref "R8") (pin "2") (pinfunction "2_2") (pintype "passive"))
      (node (ref "U$15") (pin "12") (pinfunction "GPIO18_12") (pintype "bidirectional"))
    )
    (net (code "92") (name "Net-(U$15-GPIO21)") (class "Default")
      (node (ref "R9") (pin "2") (pinfunction "2_2") (pintype "passive"))
      (node (ref "U$15") (pin "13") (pinfunction "GPIO21_13") (pintype "bidirectional"))
    )
    (net (code "93") (name "VCC") (class "Default")
      (node (ref "C6") (pin "1") (pinfunction "1_1") (pintype "passive"))
      (node (ref "C7") (pin "+") (pinfunction "+_+") (pintype "passive"))
      (node (ref "IC3") (pin "8") (pinfunction "VCC2_POWER_8") (pintype "bidirectional"))
      (node (ref "IC4") (pin "8") (pinfunction "VCC2_POWER_8") (pintype "bidirectional"))
      (node (ref "IC5") (pin "1") (pinfunction "VIN_1") (pintype "bidirectional"))
      (node (ref "IC6") (pin "1") (pinfunction "IN_1") (pintype "bidirectional"))
      (node (ref "JP2") (pin "2") (pinfunction "2_2") (pintype "passive"))
      (node (ref "Q10") (pin "2") (pinfunction "E_2") (pintype "passive"))
      (node (ref "Q20") (pin "2") (pinfunction "E_2") (pintype "passive"))
      (node (ref "Q30") (pin "2") (pinfunction "E_2") (pintype "passive"))
      (node (ref "Q40") (pin "2") (pinfunction "E_2") (pintype "passive"))
      (node (ref "R14") (pin "2") (pinfunction "2_2") (pintype "passive"))
      (node (ref "R24") (pin "2") (pinfunction "2_2") (pintype "passive"))
      (node (ref "R34") (pin "2") (pinfunction "2_2") (pintype "passive"))
      (node (ref "R44") (pin "2") (pinfunction "2_2") (pintype "passive"))
      (node (ref "R52") (pin "1") (pinfunction "1_1") (pintype "passive"))
    )
    (net (code "94") (name "unconnected-(FTDI-HEADER-Pad5)") (class "Default")
      (node (ref "FTDI-HEADER") (pin "5") (pinfunction "5_5") (pintype "passive"))
    )
    (net (code "95") (name "unconnected-(IC1-PC4(ADC4{slash}SDA{slash}PCINT12)-Pad27)") (class "Default")
      (node (ref "IC1") (pin "27") (pinfunction "PC4(ADC4/SDA/PCINT12)_27") (pintype "bidirectional"))
    )
    (net (code "96") (name "unconnected-(IC1-PC5(ADC5{slash}SCL{slash}PCINT13)-Pad28)") (class "Default")
      (node (ref "IC1") (pin "28") (pinfunction "PC5(ADC5/SCL/PCINT13)_28") (pintype "bidirectional"))
    )
    (net (code "97") (name "unconnected-(IC2-PC4(ADC4{slash}SDA{slash}PCINT12)-Pad27)") (class "Default")
      (node (ref "IC2") (pin "27") (pinfunction "PC4(ADC4/SDA/PCINT12)_27") (pintype "bidirectional"))
    )
    (net (code "98") (name "unconnected-(IC2-PC5(ADC5{slash}SCL{slash}PCINT13)-Pad28)") (class "Default")
      (node (ref "IC2") (pin "28") (pinfunction "PC5(ADC5/SCL/PCINT13)_28") (pintype "bidirectional"))
    )
    (net (code "99") (name "unconnected-(U$15-3V3-Pad17)") (class "Default")
      (node (ref "U$15") (pin "17") (pinfunction "3V3_17") (pintype "bidirectional"))
    )
    (net (code "100") (name "unconnected-(U$15-5V-Pad4)") (class "Default")
      (node (ref "U$15") (pin "4") (pinfunction "5V_4") (pintype "bidirectional"))
    )
    (net (code "101") (name "unconnected-(U$15-GND-Pad9)") (class "Default")
      (node (ref "U$15") (pin "9") (pinfunction "GND_9") (pintype "bidirectional"))
    )
    (net (code "102") (name "unconnected-(U$15-GND-Pad14)") (class "Default")
      (node (ref "U$15") (pin "14") (pinfunction "GND_14") (pintype "bidirectional"))
    )
    (net (code "103") (name "unconnected-(U$15-GND-Pad20)") (class "Default")
      (node (ref "U$15") (pin "20") (pinfunction "GND_20") (pintype "bidirectional"))
    )
    (net (code "104") (name "unconnected-(U$15-GND-Pad25)") (class "Default")
      (node (ref "U$15") (pin "25") (pinfunction "GND_25") (pintype "bidirectional"))
    )
    (net (code "105") (name "unconnected-(U$15-GPIO4,GPCLK0-Pad7)") (class "Default")
      (node (ref "U$15") (pin "7") (pinfunction "GPIO4,GPCLK0_7") (pintype "bidirectional"))
    )
    (net (code "106") (name "unconnected-(U$15-GPIO7,SPI0_CE1-Pad26)") (class "Default")
      (node (ref "U$15") (pin "26") (pinfunction "GPIO7,SPI0_CE1_26") (pintype "bidirectional"))
    )
    (net (code "107") (name "unconnected-(U$15-GPIO8,SPI0_CE0-Pad24)") (class "Default")
      (node (ref "U$15") (pin "24") (pinfunction "GPIO8,SPI0_CE0_24") (pintype "bidirectional"))
    )
    (net (code "108") (name "unconnected-(U$15-GPIO9_MISO-Pad21)") (class "Default")
      (node (ref "U$15") (pin "21") (pinfunction "GPIO9_MISO_21") (pintype "bidirectional"))
    )
    (net (code "109") (name "unconnected-(U$15-GPIO10_MOSI-Pad19)") (class "Default")
      (node (ref "U$15") (pin "19") (pinfunction "GPIO10_MOSI_19") (pintype "bidirectional"))
    )
    (net (code "110") (name "unconnected-(U$15-GPIO11_SCLK-Pad23)") (class "Default")
      (node (ref "U$15") (pin "23") (pinfunction "GPIO11_SCLK_23") (pintype "bidirectional"))
    )
    (net (code "111") (name "unconnected-(U$15-GPIO17-Pad11)") (class "Default")
      (node (ref "U$15") (pin "11") (pinfunction "GPIO17_11") (pintype "bidirectional"))
    )
    (net (code "112") (name "unconnected-(U$15-GPIO22-Pad15)") (class "Default")
      (node (ref "U$15") (pin "15") (pinfunction "GPIO22_15") (pintype "bidirectional"))
    )
    (net (code "113") (name "unconnected-(U$15-GPIO23-Pad16)") (class "Default")
      (node (ref "U$15") (pin "16") (pinfunction "GPIO23_16") (pintype "bidirectional"))
    )
    (net (code "114") (name "unconnected-(U$15-GPIO24-Pad18)") (class "Default")
      (node (ref "U$15") (pin "18") (pinfunction "GPIO24_18") (pintype "bidirectional"))
    )
    (net (code "115") (name "unconnected-(U$15-GPIO25-Pad22)") (class "Default")
      (node (ref "U$15") (pin "22") (pinfunction "GPIO25_22") (pintype "bidirectional"))
    )
  )
)
